# motor_controller_2_1.net
KiCad netlist of a schematic drawn in EAGLE
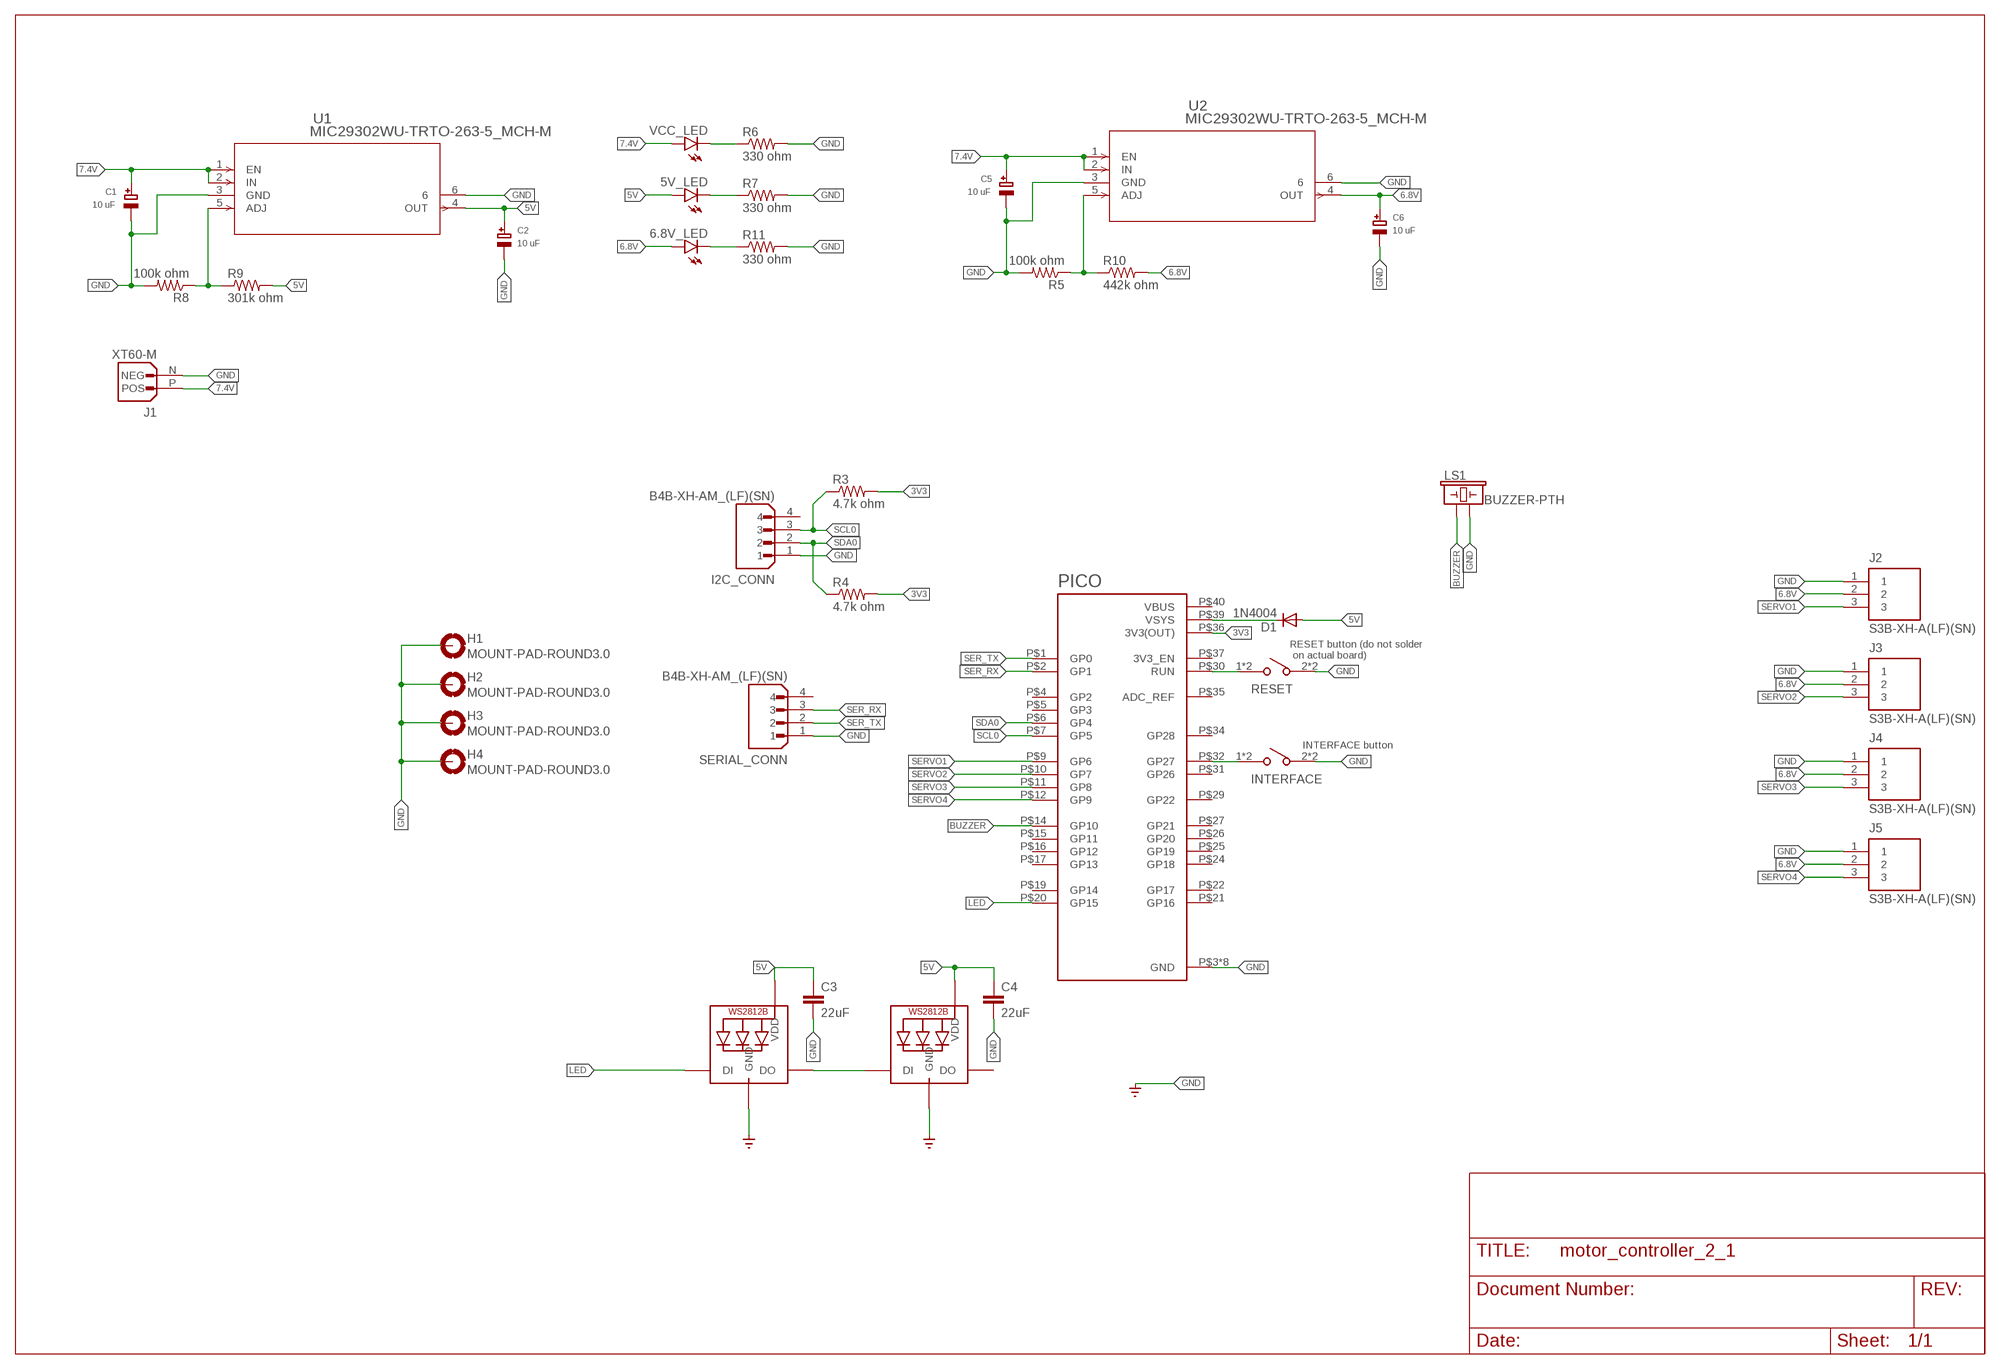
[diagram p0: schematic, sheet 1]

(export (version "E")
  (design (tool "Eeschema 10.0.6"))
  (components
    (comp (ref "5V_LED")
      (value "LEDCHIPLED_1206")
      (footprint "eagle-import:CHIPLED_1206")
      (libsource (lib "eagle-import") (part "LEDCHIPLED_1206"))
    )
    (comp (ref "6.8V_LED")
      (value "LEDCHIPLED_1206")
      (footprint "eagle-import:CHIPLED_1206")
      (libsource (lib "eagle-import") (part "LEDCHIPLED_1206"))
    )
    (comp (ref "C1")
      (value "10 uF")
      (footprint "eagle-import:EIA3216-18_A-W")
      (libsource (lib "eagle-import") (part "CAP_TANTALUMA/3216_WAVE"))
    )
    (comp (ref "C2")
      (value "10 uF")
      (footprint "eagle-import:EIA3216-18_A-W")
      (libsource (lib "eagle-import") (part "CAP_TANTALUMA/3216_WAVE"))
    )
    (comp (ref "C3")
      (value "22uF")
      (footprint "eagle-import:0805")
      (libsource (lib "eagle-import") (part "22UF-0805-16V-20%"))
    )
    (comp (ref "C4")
      (value "22uF")
      (footprint "eagle-import:0805")
      (libsource (lib "eagle-import") (part "22UF-0805-16V-20%"))
    )
    (comp (ref "C5")
      (value "10 uF")
      (footprint "eagle-import:EIA3216-18_A-W")
      (libsource (lib "eagle-import") (part "CAP_TANTALUMA/3216_WAVE"))
    )
    (comp (ref "C6")
      (value "10 uF")
      (footprint "eagle-import:EIA3216-18_A-W")
      (libsource (lib "eagle-import") (part "CAP_TANTALUMA/3216_WAVE"))
    )
    (comp (ref "D1")
      (value "1N4004")
      (footprint "eagle-import:DO41-10")
      (libsource (lib "eagle-import") (part "1N4004"))
    )
    (comp (ref "H1")
      (value "MOUNT-PAD-ROUND3.0")
      (footprint "eagle-import:3,0-PAD")
      (libsource (lib "eagle-import") (part "MOUNT-PAD-ROUND3.0"))
    )
    (comp (ref "H2")
      (value "MOUNT-PAD-ROUND3.0")
      (footprint "eagle-import:3,0-PAD")
      (libsource (lib "eagle-import") (part "MOUNT-PAD-ROUND3.0"))
    )
    (comp (ref "H3")
      (value "MOUNT-PAD-ROUND3.0")
      (footprint "eagle-import:3,0-PAD")
      (libsource (lib "eagle-import") (part "MOUNT-PAD-ROUND3.0"))
    )
    (comp (ref "H4")
      (value "MOUNT-PAD-ROUND3.0")
      (footprint "eagle-import:3,0-PAD")
      (libsource (lib "eagle-import") (part "MOUNT-PAD-ROUND3.0"))
    )
    (comp (ref "I2C_CONN")
      (value "B4B-XH-AM_(LF)(SN)")
      (footprint "eagle-import:JST_B4B-XH-AM_(LF)(SN)")
      (fields (field (name "MF") "JST Corporation") (field (name "MP") "B4B-XH-AM (LF)(SN)"))
      (libsource (lib "eagle-import") (part "B4B-XH-AM_(LF)(SN)"))
    )
    (comp (ref "INTERFACE")
      (value "TS04-66-95-BK-100-SMT")
      (footprint "eagle-import:SW_TS04-66-95-BK-100-SMT")
      (fields (field (name "MF") "CUI Devices"))
      (libsource (lib "eagle-import") (part "TS04-66-95-BK-100-SMT"))
    )
    (comp (ref "J1")
      (value "XT60-M")
      (footprint "eagle-import:AMASS_XT60-M")
      (fields (field (name "MF") "AMASS"))
      (libsource (lib "eagle-import") (part "XT60-M"))
    )
    (comp (ref "J2")
      (value "S3B-XH-A(LF)(SN)")
      (footprint "eagle-import:JST_S3B-XH-A(LF)(SN)")
      (fields (field (name "MF") "JST Sales"))
      (libsource (lib "eagle-import") (part "S3B-XH-A(LF)(SN)"))
    )
    (comp (ref "J3")
      (value "S3B-XH-A(LF)(SN)")
      (footprint "eagle-import:JST_S3B-XH-A(LF)(SN)")
      (fields (field (name "MF") "JST Sales"))
      (libsource (lib "eagle-import") (part "S3B-XH-A(LF)(SN)"))
    )
    (comp (ref "J4")
      (value "S3B-XH-A(LF)(SN)")
      (footprint "eagle-import:JST_S3B-XH-A(LF)(SN)")
      (fields (field (name "MF") "JST Sales"))
      (libsource (lib "eagle-import") (part "S3B-XH-A(LF)(SN)"))
    )
    (comp (ref "J5")
      (value "S3B-XH-A(LF)(SN)")
      (footprint "eagle-import:JST_S3B-XH-A(LF)(SN)")
      (fields (field (name "MF") "JST Sales"))
      (libsource (lib "eagle-import") (part "S3B-XH-A(LF)(SN)"))
    )
    (comp (ref "LED1")
      (value "WS2812B3535")
      (footprint "eagle-import:LED3535")
      (fields (field (name "MF") "Worldsemi") (field (name "MP") "WS2812B"))
      (libsource (lib "eagle-import") (part "WS2812B3535"))
    )
    (comp (ref "LED2")
      (value "WS2812B3535")
      (footprint "eagle-import:LED3535")
      (fields (field (name "MF") "Worldsemi") (field (name "MP") "WS2812B"))
      (libsource (lib "eagle-import") (part "WS2812B3535"))
    )
    (comp (ref "LS1")
      (value "BUZZER-PTH")
      (footprint "eagle-import:BUZZER-12MM")
      (libsource (lib "eagle-import") (part "BUZZER-PTH"))
    )
    (comp (ref "PICO")
      (value "RASPBERRY_PICO-NO_DEBUG")
      (footprint "eagle-import:PICO-PKG-NO_DEBUG")
      (libsource (lib "eagle-import") (part "RASPBERRY_PICO-NO_DEBUG"))
    )
    (comp (ref "R3")
      (value "4.7k ohm")
      (footprint "eagle-import:R0805")
      (libsource (lib "eagle-import") (part "R-US_R0805"))
    )
    (comp (ref "R4")
      (value "4.7k ohm")
      (footprint "eagle-import:R0805")
      (libsource (lib "eagle-import") (part "R-US_R0805"))
    )
    (comp (ref "R5")
      (value "100k ohm")
      (footprint "eagle-import:R0805")
      (libsource (lib "eagle-import") (part "R-US_R0805"))
    )
    (comp (ref "R6")
      (value "330 ohm")
      (footprint "eagle-import:R0805")
      (libsource (lib "eagle-import") (part "R-US_R0805"))
    )
    (comp (ref "R7")
      (value "330 ohm")
      (footprint "eagle-import:R0805")
      (libsource (lib "eagle-import") (part "R-US_R0805"))
    )
    (comp (ref "R8")
      (value "100k ohm")
      (footprint "eagle-import:R0805")
      (libsource (lib "eagle-import") (part "R-US_R0805"))
    )
    (comp (ref "R9")
      (value "301k ohm")
      (footprint "eagle-import:R0805")
      (libsource (lib "eagle-import") (part "R-US_R0805"))
    )
    (comp (ref "R10")
      (value "442k ohm")
      (footprint "eagle-import:R0805")
      (libsource (lib "eagle-import") (part "R-US_R0805"))
    )
    (comp (ref "R11")
      (value "330 ohm")
      (footprint "eagle-import:R0805")
      (libsource (lib "eagle-import") (part "R-US_R0805"))
    )
    (comp (ref "RESET")
      (value "TS04-66-95-BK-100-SMT")
      (footprint "eagle-import:SW_TS04-66-95-BK-100-SMT")
      (fields (field (name "MF") "CUI Devices"))
      (libsource (lib "eagle-import") (part "TS04-66-95-BK-100-SMT"))
    )
    (comp (ref "SERIAL_CONN")
      (value "B4B-XH-AM_(LF)(SN)")
      (footprint "eagle-import:JST_B4B-XH-AM_(LF)(SN)")
      (fields (field (name "MF") "JST Corporation") (field (name "MP") "B4B-XH-AM (LF)(SN)"))
      (libsource (lib "eagle-import") (part "B4B-XH-AM_(LF)(SN)"))
    )
    (comp (ref "U1")
      (value "MIC29302WU-TRTO-263-5_MCH-M")
      (footprint "eagle-import:TO-263-5_MCH-M")
      (fields
        (field (name "MANUFACTURER_PART_NUMBER") "MIC29302WU-TR")
        (field (name "COPYRIGHT") "Copyright (C) 2024 Ultra Librarian. All rights reserved.")
      )
      (libsource (lib "eagle-import") (part "MIC29302WU-TRTO-263-5_MCH-M"))
    )
    (comp (ref "U2")
      (value "MIC29302WU-TRTO-263-5_MCH-M")
      (footprint "eagle-import:TO-263-5_MCH-M")
      (fields
        (field (name "MANUFACTURER_PART_NUMBER") "MIC29302WU-TR")
        (field (name "COPYRIGHT") "Copyright (C) 2024 Ultra Librarian. All rights reserved.")
      )
      (libsource (lib "eagle-import") (part "MIC29302WU-TRTO-263-5_MCH-M"))
    )
    (comp (ref "VCC_LED")
      (value "LEDCHIPLED_1206")
      (footprint "eagle-import:CHIPLED_1206")
      (libsource (lib "eagle-import") (part "LEDCHIPLED_1206"))
    )
  )
  (nets
    (net (code "1") (name "/VBUS") (class "Default")
      (node (ref "PICO") (pin "P$40") (pinfunction "VBUS_P$40") (pintype "power_in"))
    )
    (net (code "2") (name "3V3") (class "Default")
      (node (ref "PICO") (pin "P$36") (pinfunction "3V3(OUT)_P$36") (pintype "power_in"))
      (node (ref "R3") (pin "2") (pinfunction "2_2") (pintype "passive"))
      (node (ref "R4") (pin "2") (pinfunction "2_2") (pintype "passive"))
    )
    (net (code "3") (name "5V") (class "Default")
      (node (ref "5V_LED") (pin "A") (pinfunction "A_A") (pintype "passive"))
      (node (ref "C2") (pin "+") (pinfunction "+_+") (pintype "passive"))
      (node (ref "C3") (pin "1") (pinfunction "1_1") (pintype "passive"))
      (node (ref "C4") (pin "1") (pinfunction "1_1") (pintype "passive"))
      (node (ref "D1") (pin "A") (pinfunction "A_A") (pintype "passive"))
      (node (ref "LED1") (pin "2") (pinfunction "VDD_2") (pintype "power_in"))
      (node (ref "LED2") (pin "2") (pinfunction "VDD_2") (pintype "power_in"))
      (node (ref "R9") (pin "2") (pinfunction "2_2") (pintype "passive"))
      (node (ref "U1") (pin "4") (pinfunction "OUT_4") (pintype "output"))
    )
    (net (code "4") (name "6.8V") (class "Default")
      (node (ref "6.8V_LED") (pin "A") (pinfunction "A_A") (pintype "passive"))
      (node (ref "C6") (pin "+") (pinfunction "+_+") (pintype "passive"))
      (node (ref "J2") (pin "2") (pinfunction "2_2") (pintype "passive"))
      (node (ref "J3") (pin "2") (pinfunction "2_2") (pintype "passive"))
      (node (ref "J4") (pin "2") (pinfunction "2_2") (pintype "passive"))
      (node (ref "J5") (pin "2") (pinfunction "2_2") (pintype "passive"))
      (node (ref "R10") (pin "2") (pinfunction "2_2") (pintype "passive"))
      (node (ref "U2") (pin "4") (pinfunction "OUT_4") (pintype "output"))
    )
    (net (code "5") (name "7.4V") (class "Default")
      (node (ref "C1") (pin "+") (pinfunction "+_+") (pintype "passive"))
      (node (ref "C5") (pin "+") (pinfunction "+_+") (pintype "passive"))
      (node (ref "J1") (pin "P") (pinfunction "POS_P") (pintype "passive"))
      (node (ref "U1") (pin "1") (pinfunction "EN_1") (pintype "input"))
      (node (ref "U1") (pin "2") (pinfunction "IN_2") (pintype "input"))
      (node (ref "U2") (pin "1") (pinfunction "EN_1") (pintype "input"))
      (node (ref "U2") (pin "2") (pinfunction "IN_2") (pintype "input"))
      (node (ref "VCC_LED") (pin "A") (pinfunction "A_A") (pintype "passive"))
    )
    (net (code "6") (name "BUZZER") (class "Default")
      (node (ref "LS1") (pin "+") (pinfunction "1_+") (pintype "passive"))
      (node (ref "PICO") (pin "P$14") (pinfunction "GP10_P$14") (pintype "bidirectional"))
    )
    (net (code "7") (name "GND") (class "Default")
      (node (ref "C1") (pin "-") (pinfunction "-_-") (pintype "passive"))
      (node (ref "C2") (pin "-") (pinfunction "-_-") (pintype "passive"))
      (node (ref "C3") (pin "2") (pinfunction "2_2") (pintype "passive"))
      (node (ref "C4") (pin "2") (pinfunction "2_2") (pintype "passive"))
      (node (ref "C5") (pin "-") (pinfunction "-_-") (pintype "passive"))
      (node (ref "C6") (pin "-") (pinfunction "-_-") (pintype "passive"))
      (node (ref "H1") (pin "B3,0") (pinfunction "MOUNT_B3,0") (pintype "passive"))
      (node (ref "H2") (pin "B3,0") (pinfunction "MOUNT_B3,0") (pintype "passive"))
      (node (ref "H3") (pin "B3,0") (pinfunction "MOUNT_B3,0") (pintype "passive"))
      (node (ref "H4") (pin "B3,0") (pinfunction "MOUNT_B3,0") (pintype "passive"))
      (node (ref "I2C_CONN") (pin "1") (pinfunction "1_1") (pintype "passive"))
      (node (ref "INTERFACE") (pin "2") (pinfunction "4_2") (pintype "passive"))
      (node (ref "INTERFACE") (pin "4") (pinfunction "4_4") (pintype "passive"))
      (node (ref "J1") (pin "N") (pinfunction "NEG_N") (pintype "passive"))
      (node (ref "J2") (pin "1") (pinfunction "1_1") (pintype "passive"))
      (node (ref "J3") (pin "1") (pinfunction "1_1") (pintype "passive"))
      (node (ref "J4") (pin "1") (pinfunction "1_1") (pintype "passive"))
      (node (ref "J5") (pin "1") (pinfunction "1_1") (pintype "passive"))
      (node (ref "LED1") (pin "4") (pinfunction "GND_4") (pintype "power_in"))
      (node (ref "LED2") (pin "4") (pinfunction "GND_4") (pintype "power_in"))
      (node (ref "LS1") (pin "-") (pinfunction "2_-") (pintype "passive"))
      (node (ref "PICO") (pin "P$13") (pinfunction "GND_P$13") (pintype "power_in"))
      (node (ref "PICO") (pin "P$18") (pinfunction "GND_P$18") (pintype "power_in"))
      (node (ref "PICO") (pin "P$23") (pinfunction "GND_P$23") (pintype "power_in"))
      (node (ref "PICO") (pin "P$28") (pinfunction "GND_P$28") (pintype "power_in"))
      (node (ref "PICO") (pin "P$3") (pinfunction "GND_P$3") (pintype "power_in"))
      (node (ref "PICO") (pin "P$33") (pinfunction "GND_P$33") (pintype "power_in"))
      (node (ref "PICO") (pin "P$38") (pinfunction "GND_P$38") (pintype "power_in"))
      (node (ref "PICO") (pin "P$8") (pinfunction "GND_P$8") (pintype "power_in"))
      (node (ref "R11") (pin "2") (pinfunction "2_2") (pintype "passive"))
      (node (ref "R5") (pin "2") (pinfunction "2_2") (pintype "passive"))
      (node (ref "R6") (pin "2") (pinfunction "2_2") (pintype "passive"))
      (node (ref "R7") (pin "2") (pinfunction "2_2") (pintype "passive"))
      (node (ref "R8") (pin "2") (pinfunction "2_2") (pintype "passive"))
      (node (ref "RESET") (pin "2") (pinfunction "4_2") (pintype "passive"))
      (node (ref "RESET") (pin "4") (pinfunction "4_4") (pintype "passive"))
      (node (ref "SERIAL_CONN") (pin "1") (pinfunction "1_1") (pintype "passive"))
      (node (ref "U1") (pin "3") (pinfunction "GND_3") (pintype "power_in"))
      (node (ref "U1") (pin "6") (pinfunction "6_6") (pintype "passive"))
      (node (ref "U2") (pin "3") (pinfunction "GND_3") (pintype "power_in"))
      (node (ref "U2") (pin "6") (pinfunction "6_6") (pintype "passive"))
    )
    (net (code "8") (name "LED") (class "Default")
      (node (ref "LED1") (pin "1") (pinfunction "DI_1") (pintype "input"))
      (node (ref "PICO") (pin "P$20") (pinfunction "GP15_P$20") (pintype "bidirectional"))
    )
    (net (code "9") (name "Net-(5V_LED-PadC)") (class "Default")
      (node (ref "5V_LED") (pin "C") (pinfunction "C_C") (pintype "passive"))
      (node (ref "R7") (pin "1") (pinfunction "1_1") (pintype "passive"))
    )
    (net (code "10") (name "Net-(6.8V_LED-PadC)") (class "Default")
      (node (ref "6.8V_LED") (pin "C") (pinfunction "C_C") (pintype "passive"))
      (node (ref "R11") (pin "1") (pinfunction "1_1") (pintype "passive"))
    )
    (net (code "11") (name "Net-(LED1-DO)") (class "Default")
      (node (ref "LED1") (pin "3") (pinfunction "DO_3") (pintype "output"))
      (node (ref "LED2") (pin "1") (pinfunction "DI_1") (pintype "input"))
    )
    (net (code "12") (name "Net-(PICO-GP27)") (class "Default")
      (node (ref "INTERFACE") (pin "1") (pinfunction "2_1") (pintype "passive"))
      (node (ref "INTERFACE") (pin "3") (pinfunction "2_3") (pintype "passive"))
      (node (ref "PICO") (pin "P$32") (pinfunction "GP27_P$32") (pintype "bidirectional"))
    )
    (net (code "13") (name "Net-(PICO-RUN)") (class "Default")
      (node (ref "PICO") (pin "P$30") (pinfunction "RUN_P$30") (pintype "input"))
      (node (ref "RESET") (pin "1") (pinfunction "2_1") (pintype "passive"))
      (node (ref "RESET") (pin "3") (pinfunction "2_3") (pintype "passive"))
    )
    (net (code "14") (name "Net-(PICO-VSYS)") (class "Default")
      (node (ref "D1") (pin "C") (pinfunction "C_C") (pintype "passive"))
      (node (ref "PICO") (pin "P$39") (pinfunction "VSYS_P$39") (pintype "power_in"))
    )
    (net (code "15") (name "Net-(R6-Pad1)") (class "Default")
      (node (ref "R6") (pin "1") (pinfunction "1_1") (pintype "passive"))
      (node (ref "VCC_LED") (pin "C") (pinfunction "C_C") (pintype "passive"))
    )
    (net (code "16") (name "Net-(U1-ADJ)") (class "Default")
      (node (ref "R8") (pin "1") (pinfunction "1_1") (pintype "passive"))
      (node (ref "R9") (pin "1") (pinfunction "1_1") (pintype "passive"))
      (node (ref "U1") (pin "5") (pinfunction "ADJ_5") (pintype "input"))
    )
    (net (code "17") (name "Net-(U2-ADJ)") (class "Default")
      (node (ref "R10") (pin "1") (pinfunction "1_1") (pintype "passive"))
      (node (ref "R5") (pin "1") (pinfunction "1_1") (pintype "passive"))
      (node (ref "U2") (pin "5") (pinfunction "ADJ_5") (pintype "input"))
    )
    (net (code "18") (name "SCL0") (class "Default")
      (node (ref "I2C_CONN") (pin "3") (pinfunction "3_3") (pintype "passive"))
      (node (ref "PICO") (pin "P$7") (pinfunction "GP5_P$7") (pintype "bidirectional"))
      (node (ref "R3") (pin "1") (pinfunction "1_1") (pintype "passive"))
    )
    (net (code "19") (name "SDA0") (class "Default")
      (node (ref "I2C_CONN") (pin "2") (pinfunction "2_2") (pintype "passive"))
      (node (ref "PICO") (pin "P$6") (pinfunction "GP4_P$6") (pintype "bidirectional"))
      (node (ref "R4") (pin "1") (pinfunction "1_1") (pintype "passive"))
    )
    (net (code "20") (name "SERVO1") (class "Default")
      (node (ref "J2") (pin "3") (pinfunction "3_3") (pintype "passive"))
      (node (ref "PICO") (pin "P$9") (pinfunction "GP6_P$9") (pintype "bidirectional"))
    )
    (net (code "21") (name "SERVO2") (class "Default")
      (node (ref "J3") (pin "3") (pinfunction "3_3") (pintype "passive"))
      (node (ref "PICO") (pin "P$10") (pinfunction "GP7_P$10") (pintype "bidirectional"))
    )
    (net (code "22") (name "SERVO3") (class "Default")
      (node (ref "J4") (pin "3") (pinfunction "3_3") (pintype "passive"))
      (node (ref "PICO") (pin "P$11") (pinfunction "GP8_P$11") (pintype "bidirectional"))
    )
    (net (code "23") (name "SERVO4") (class "Default")
      (node (ref "J5") (pin "3") (pinfunction "3_3") (pintype "passive"))
      (node (ref "PICO") (pin "P$12") (pinfunction "GP9_P$12") (pintype "bidirectional"))
    )
    (net (code "24") (name "SER_RX") (class "Default")
      (node (ref "PICO") (pin "P$2") (pinfunction "GP1_P$2") (pintype "bidirectional"))
      (node (ref "SERIAL_CONN") (pin "3") (pinfunction "3_3") (pintype "passive"))
    )
    (net (code "25") (name "SER_TX") (class "Default")
      (node (ref "PICO") (pin "P$1") (pinfunction "GP0_P$1") (pintype "bidirectional"))
      (node (ref "SERIAL_CONN") (pin "2") (pinfunction "2_2") (pintype "passive"))
    )
    (net (code "26") (name "unconnected-(I2C_CONN-Pad4)") (class "Default")
      (node (ref "I2C_CONN") (pin "4") (pinfunction "4_4") (pintype "passive"))
    )
    (net (code "27") (name "unconnected-(LED2-DO-Pad3)") (class "Default")
      (node (ref "LED2") (pin "3") (pinfunction "DO_3") (pintype "output"))
    )
    (net (code "28") (name "unconnected-(PICO-3V3_EN-PadP$37)") (class "Default")
      (node (ref "PICO") (pin "P$37") (pinfunction "3V3_EN_P$37") (pintype "input"))
    )
    (net (code "29") (name "unconnected-(PICO-ADC_REF-PadP$35)") (class "Default")
      (node (ref "PICO") (pin "P$35") (pinfunction "ADC_REF_P$35") (pintype "input"))
    )
    (net (code "30") (name "unconnected-(PICO-GP2-PadP$4)") (class "Default")
      (node (ref "PICO") (pin "P$4") (pinfunction "GP2_P$4") (pintype "bidirectional"))
    )
    (net (code "31") (name "unconnected-(PICO-GP3-PadP$5)") (class "Default")
      (node (ref "PICO") (pin "P$5") (pinfunction "GP3_P$5") (pintype "bidirectional"))
    )
    (net (code "32") (name "unconnected-(PICO-GP11-PadP$15)") (class "Default")
      (node (ref "PICO") (pin "P$15") (pinfunction "GP11_P$15") (pintype "bidirectional"))
    )
    (net (code "33") (name "unconnected-(PICO-GP12-PadP$16)") (class "Default")
      (node (ref "PICO") (pin "P$16") (pinfunction "GP12_P$16") (pintype "bidirectional"))
    )
    (net (code "34") (name "unconnected-(PICO-GP13-PadP$17)") (class "Default")
      (node (ref "PICO") (pin "P$17") (pinfunction "GP13_P$17") (pintype "bidirectional"))
    )
    (net (code "35") (name "unconnected-(PICO-GP14-PadP$19)") (class "Default")
      (node (ref "PICO") (pin "P$19") (pinfunction "GP14_P$19") (pintype "bidirectional"))
    )
    (net (code "36") (name "unconnected-(PICO-GP16-PadP$21)") (class "Default")
      (node (ref "PICO") (pin "P$21") (pinfunction "GP16_P$21") (pintype "bidirectional"))
    )
    (net (code "37") (name "unconnected-(PICO-GP17-PadP$22)") (class "Default")
      (node (ref "PICO") (pin "P$22") (pinfunction "GP17_P$22") (pintype "bidirectional"))
    )
    (net (code "38") (name "unconnected-(PICO-GP18-PadP$24)") (class "Default")
      (node (ref "PICO") (pin "P$24") (pinfunction "GP18_P$24") (pintype "bidirectional"))
    )
    (net (code "39") (name "unconnected-(PICO-GP19-PadP$25)") (class "Default")
      (node (ref "PICO") (pin "P$25") (pinfunction "GP19_P$25") (pintype "bidirectional"))
    )
    (net (code "40") (name "unconnected-(PICO-GP20-PadP$26)") (class "Default")
      (node (ref "PICO") (pin "P$26") (pinfunction "GP20_P$26") (pintype "bidirectional"))
    )
    (net (code "41") (name "unconnected-(PICO-GP21-PadP$27)") (class "Default")
      (node (ref "PICO") (pin "P$27") (pinfunction "GP21_P$27") (pintype "bidirectional"))
    )
    (net (code "42") (name "unconnected-(PICO-GP22-PadP$29)") (class "Default")
      (node (ref "PICO") (pin "P$29") (pinfunction "GP22_P$29") (pintype "bidirectional"))
    )
    (net (code "43") (name "unconnected-(PICO-GP26-PadP$31)") (class "Default")
      (node (ref "PICO") (pin "P$31") (pinfunction "GP26_P$31") (pintype "bidirectional"))
    )
    (net (code "44") (name "unconnected-(PICO-GP28-PadP$34)") (class "Default")
      (node (ref "PICO") (pin "P$34") (pinfunction "GP28_P$34") (pintype "bidirectional"))
    )
    (net (code "45") (name "unconnected-(SERIAL_CONN-Pad4)") (class "Default")
      (node (ref "SERIAL_CONN") (pin "4") (pinfunction "4_4") (pintype "passive"))
    )
  )
)
